# REV1.net
KiCad netlist of a schematic drawn in EAGLE
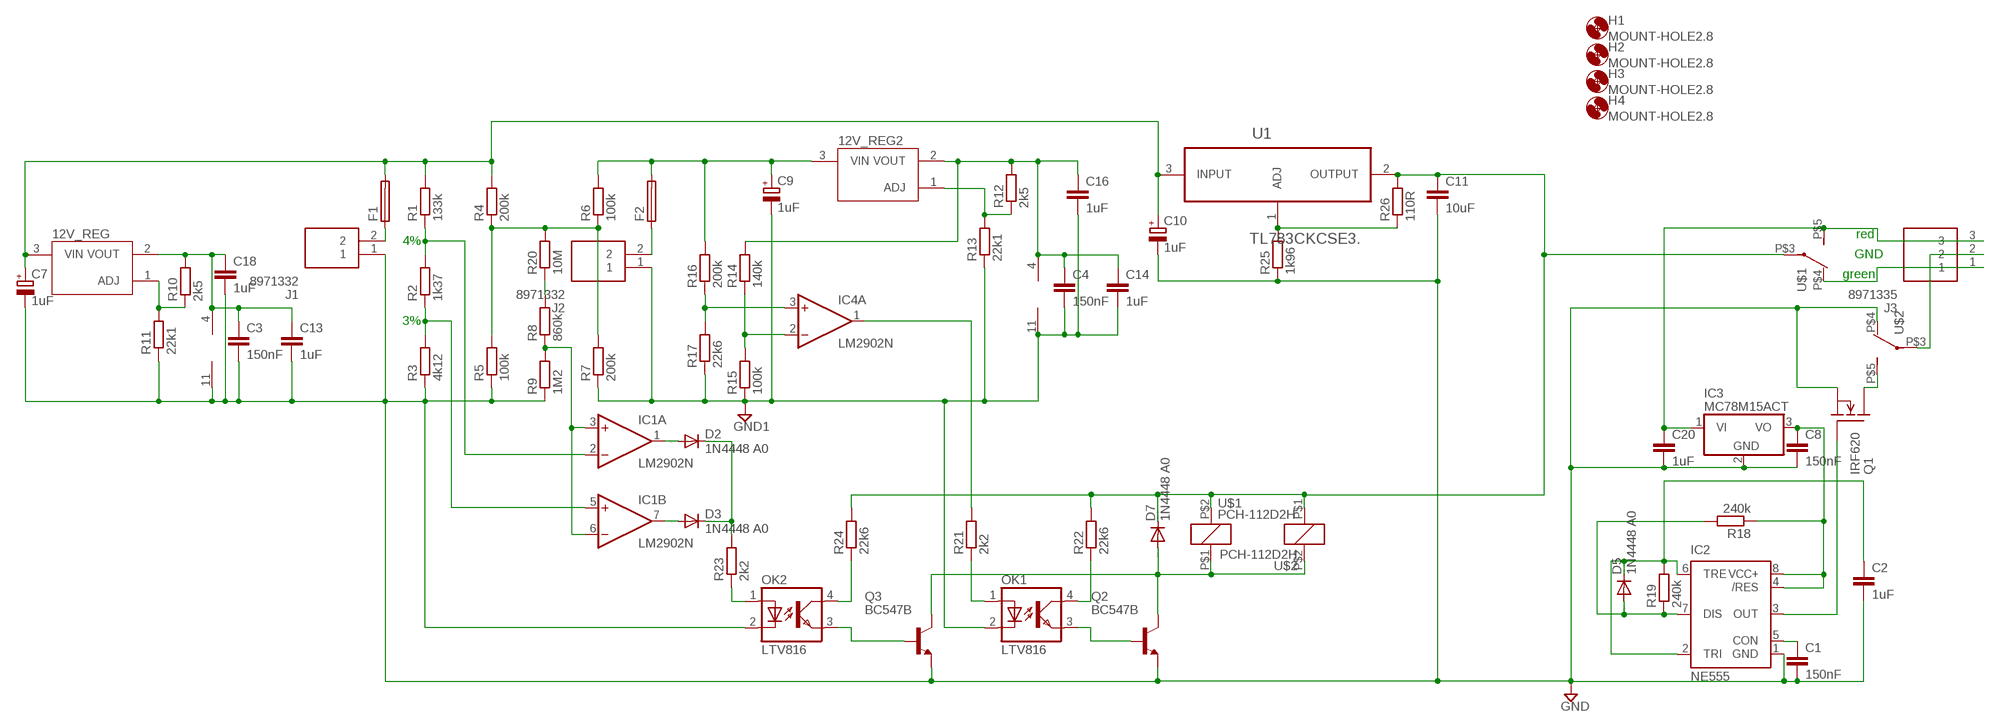
[diagram p0: schematic, sheet 1]

(export (version "E")
  (design (tool "Eeschema 10.0.6"))
  (components
    (comp (ref "12V_REG")
      (value "LR8LR8")
      (footprint "eagle-import:TO92-LINE")
      (libsource (lib "eagle-import") (part "LR8LR8"))
    )
    (comp (ref "12V_REG2")
      (value "LR8LR8")
      (footprint "eagle-import:TO92-LINE")
      (libsource (lib "eagle-import") (part "LR8LR8"))
    )
    (comp (ref "C1")
      (value "150nF")
      (footprint "eagle-import:C050-024X044")
      (libsource (lib "eagle-import") (part "C-EU050-024X044"))
    )
    (comp (ref "C2")
      (value "1uF")
      (footprint "eagle-import:C025-030X050")
      (libsource (lib "eagle-import") (part "C-EU025-030X050"))
    )
    (comp (ref "C3")
      (value "150nF")
      (footprint "eagle-import:C050-024X044")
      (libsource (lib "eagle-import") (part "C-EU050-024X044"))
    )
    (comp (ref "C4")
      (value "150nF")
      (footprint "eagle-import:C050-024X044")
      (libsource (lib "eagle-import") (part "C-EU050-024X044"))
    )
    (comp (ref "C7")
      (value "1uF")
      (footprint "eagle-import:E3,5-8")
      (libsource (lib "eagle-import") (part "CPOL-EUE3.5-8"))
    )
    (comp (ref "C8")
      (value "150nF")
      (footprint "eagle-import:C050-024X044")
      (libsource (lib "eagle-import") (part "C-EU050-024X044"))
    )
    (comp (ref "C9")
      (value "1uF")
      (footprint "eagle-import:E3,5-8")
      (libsource (lib "eagle-import") (part "CPOL-EUE3.5-8"))
    )
    (comp (ref "C10")
      (value "1uF")
      (footprint "eagle-import:E3,5-8")
      (libsource (lib "eagle-import") (part "CPOL-EUE3.5-8"))
    )
    (comp (ref "C11")
      (value "10uF")
      (footprint "eagle-import:C050-075X075")
      (libsource (lib "eagle-import") (part "C-EU050-075X075"))
    )
    (comp (ref "C13")
      (value "1uF")
      (footprint "eagle-import:C025-030X050")
      (libsource (lib "eagle-import") (part "C-EU025-030X050"))
    )
    (comp (ref "C14")
      (value "1uF")
      (footprint "eagle-import:C025-030X050")
      (libsource (lib "eagle-import") (part "C-EU025-030X050"))
    )
    (comp (ref "C16")
      (value "1uF")
      (footprint "eagle-import:C025-030X050")
      (libsource (lib "eagle-import") (part "C-EU025-030X050"))
    )
    (comp (ref "C18")
      (value "1uF")
      (footprint "eagle-import:C025-030X050")
      (libsource (lib "eagle-import") (part "C-EU025-030X050"))
    )
    (comp (ref "C20")
      (value "1uF")
      (footprint "eagle-import:C025-030X050")
      (libsource (lib "eagle-import") (part "C-EU025-030X050"))
    )
    (comp (ref "D2")
      (value "1N4448 A0")
      (footprint "eagle-import:DO35-10")
      (libsource (lib "eagle-import") (part "1N4446"))
    )
    (comp (ref "D3")
      (value "1N4448 A0")
      (footprint "eagle-import:DO35-10")
      (libsource (lib "eagle-import") (part "1N4446"))
    )
    (comp (ref "D5")
      (value "1N4448 A0")
      (footprint "eagle-import:DO35-10")
      (libsource (lib "eagle-import") (part "1N4446"))
    )
    (comp (ref "D7")
      (value "1N4448 A0")
      (footprint "eagle-import:DO35-10")
      (libsource (lib "eagle-import") (part "1N4446"))
    )
    (comp (ref "F1")
      (value "GSH15")
      (footprint "eagle-import:GSH15")
      (fields (field (name "MPN") "64900001039"))
      (libsource (lib "eagle-import") (part "GSH15"))
    )
    (comp (ref "F2")
      (value "GSH15")
      (footprint "eagle-import:GSH15")
      (fields (field (name "MPN") "64900001039"))
      (libsource (lib "eagle-import") (part "GSH15"))
    )
    (comp (ref "H1")
      (value "MOUNT-HOLE2.8")
      (footprint "eagle-import:2,8")
      (libsource (lib "eagle-import") (part "MOUNT-HOLE2.8"))
    )
    (comp (ref "H2")
      (value "MOUNT-HOLE2.8")
      (footprint "eagle-import:2,8")
      (libsource (lib "eagle-import") (part "MOUNT-HOLE2.8"))
    )
    (comp (ref "H3")
      (value "MOUNT-HOLE2.8")
      (footprint "eagle-import:2,8")
      (libsource (lib "eagle-import") (part "MOUNT-HOLE2.8"))
    )
    (comp (ref "H4")
      (value "MOUNT-HOLE2.8")
      (footprint "eagle-import:2,8")
      (libsource (lib "eagle-import") (part "MOUNT-HOLE2.8"))
    )
    (comp (ref "IC1")
      (value "LM2902N")
      (footprint "eagle-import:DIL14")
      (libsource (lib "eagle-import") (part "LM2902N"))
    )
    (comp (ref "IC2")
      (value "NE555")
      (footprint "eagle-import:DIL-08")
      (fields (field (name "MF") "Arrow Electronics") (field (name "MPN") "NE555N"))
      (libsource (lib "eagle-import") (part "NE555"))
    )
    (comp (ref "IC3")
      (value "MC78M15ACT")
      (footprint "eagle-import:TO220V")
      (libsource (lib "eagle-import") (part "MC78MT15AC"))
    )
    (comp (ref "IC4")
      (value "LM2902N")
      (footprint "eagle-import:DIL14")
      (libsource (lib "eagle-import") (part "LM2902N"))
    )
    (comp (ref "J1")
      (value "8971332")
      (footprint "eagle-import:SHDR2W90P0X350_1X2_700X700X850")
      (libsource (lib "eagle-import") (part "8971332"))
    )
    (comp (ref "J2")
      (value "8971332")
      (footprint "eagle-import:SHDR2W90P0X350_1X2_700X700X850")
      (libsource (lib "eagle-import") (part "8971332"))
    )
    (comp (ref "J3")
      (value "8971335")
      (footprint "eagle-import:SHDR3W90P0X350_1X3_1050X700X85")
      (libsource (lib "eagle-import") (part "8971335"))
    )
    (comp (ref "OK1")
      (value "LTV816")
      (footprint "eagle-import:DIL04")
      (libsource (lib "eagle-import") (part "LTV816"))
    )
    (comp (ref "OK2")
      (value "LTV816")
      (footprint "eagle-import:DIL04")
      (libsource (lib "eagle-import") (part "LTV816"))
    )
    (comp (ref "Q1")
      (value "IRF620")
      (footprint "eagle-import:TO220")
      (libsource (lib "eagle-import") (part "IRF620"))
    )
    (comp (ref "Q2")
      (value "BC547B")
      (footprint "eagle-import:TO92")
      (libsource (lib "eagle-import") (part "BC547B"))
    )
    (comp (ref "Q3")
      (value "BC547B")
      (footprint "eagle-import:TO92")
      (libsource (lib "eagle-import") (part "BC547B"))
    )
    (comp (ref "R1")
      (value "133k")
      (footprint "eagle-import:0207_10")
      (libsource (lib "eagle-import") (part "R-EU_0207/10"))
    )
    (comp (ref "R2")
      (value "1k37")
      (footprint "eagle-import:0207_10")
      (libsource (lib "eagle-import") (part "R-EU_0207/10"))
    )
    (comp (ref "R3")
      (value "4k12")
      (footprint "eagle-import:0207_10")
      (libsource (lib "eagle-import") (part "R-EU_0207/10"))
    )
    (comp (ref "R4")
      (value "200k")
      (footprint "eagle-import:0207_10")
      (libsource (lib "eagle-import") (part "R-EU_0207/10"))
    )
    (comp (ref "R5")
      (value "100k")
      (footprint "eagle-import:0207_10")
      (libsource (lib "eagle-import") (part "R-EU_0207/10"))
    )
    (comp (ref "R6")
      (value "100k")
      (footprint "eagle-import:0207_10")
      (libsource (lib "eagle-import") (part "R-EU_0207/10"))
    )
    (comp (ref "R7")
      (value "200k")
      (footprint "eagle-import:0207_10")
      (libsource (lib "eagle-import") (part "R-EU_0207/10"))
    )
    (comp (ref "R8")
      (value "860k")
      (footprint "eagle-import:0207_10")
      (libsource (lib "eagle-import") (part "R-EU_0207/10"))
    )
    (comp (ref "R9")
      (value "1M2")
      (footprint "eagle-import:0207_10")
      (libsource (lib "eagle-import") (part "R-EU_0207/10"))
    )
    (comp (ref "R10")
      (value "2k5")
      (footprint "eagle-import:0207_10")
      (libsource (lib "eagle-import") (part "R-EU_0207/10"))
    )
    (comp (ref "R11")
      (value "22k1")
      (footprint "eagle-import:0207_10")
      (libsource (lib "eagle-import") (part "R-EU_0207/10"))
    )
    (comp (ref "R12")
      (value "2k5")
      (footprint "eagle-import:0207_10")
      (libsource (lib "eagle-import") (part "R-EU_0207/10"))
    )
    (comp (ref "R13")
      (value "22k1")
      (footprint "eagle-import:0207_10")
      (libsource (lib "eagle-import") (part "R-EU_0207/10"))
    )
    (comp (ref "R14")
      (value "140k")
      (footprint "eagle-import:0207_10")
      (libsource (lib "eagle-import") (part "R-EU_0207/10"))
    )
    (comp (ref "R15")
      (value "100k")
      (footprint "eagle-import:0207_10")
      (libsource (lib "eagle-import") (part "R-EU_0207/10"))
    )
    (comp (ref "R16")
      (value "200k")
      (footprint "eagle-import:0207_10")
      (libsource (lib "eagle-import") (part "R-EU_0207/10"))
    )
    (comp (ref "R17")
      (value "22k6")
      (footprint "eagle-import:0207_10")
      (libsource (lib "eagle-import") (part "R-EU_0207/10"))
    )
    (comp (ref "R18")
      (value "240k")
      (footprint "eagle-import:0207_10")
      (libsource (lib "eagle-import") (part "R-EU_0207/10"))
    )
    (comp (ref "R19")
      (value "240k")
      (footprint "eagle-import:0207_10")
      (libsource (lib "eagle-import") (part "R-EU_0207/10"))
    )
    (comp (ref "R20")
      (value "10M")
      (footprint "eagle-import:0207_10")
      (libsource (lib "eagle-import") (part "R-EU_0207/10"))
    )
    (comp (ref "R21")
      (value "2k2")
      (footprint "eagle-import:0207_10")
      (libsource (lib "eagle-import") (part "R-EU_0207/10"))
    )
    (comp (ref "R22")
      (value "22k6")
      (footprint "eagle-import:0207_10")
      (libsource (lib "eagle-import") (part "R-EU_0207/10"))
    )
    (comp (ref "R23")
      (value "2k2")
      (footprint "eagle-import:0207_10")
      (libsource (lib "eagle-import") (part "R-EU_0207/10"))
    )
    (comp (ref "R24")
      (value "22k6")
      (footprint "eagle-import:0207_10")
      (libsource (lib "eagle-import") (part "R-EU_0207/10"))
    )
    (comp (ref "R25")
      (value "1k96")
      (footprint "eagle-import:0309_10")
      (libsource (lib "eagle-import") (part "R-EU_0309/10"))
    )
    (comp (ref "R26")
      (value "110R")
      (footprint "eagle-import:0309_10")
      (libsource (lib "eagle-import") (part "R-EU_0309/10"))
    )
    (comp (ref "U$1")
      (value "PCH-112D2H")
      (footprint "eagle-import:PCH-112D2H")
      (libsource (lib "eagle-import") (part "PCH-112D2H"))
    )
    (comp (ref "U$2")
      (value "PCH-112D2H")
      (footprint "eagle-import:PCH-112D2H")
      (libsource (lib "eagle-import") (part "PCH-112D2H"))
    )
    (comp (ref "U1")
      (value "TL783CKCSE3.")
      (footprint "eagle-import:TO254P457X1016X2222-3P")
      (libsource (lib "eagle-import") (part "TL783CKCSE3."))
    )
  )
  (nets
    (net (code "1") (name "GND") (class "Default")
      (node (ref "C1") (pin "2") (pinfunction "2_2") (pintype "passive"))
      (node (ref "C10") (pin "-") (pinfunction "-_-") (pintype "passive"))
      (node (ref "C11") (pin "2") (pinfunction "2_2") (pintype "passive"))
      (node (ref "C13") (pin "2") (pinfunction "2_2") (pintype "passive"))
      (node (ref "C18") (pin "2") (pinfunction "2_2") (pintype "passive"))
      (node (ref "C2") (pin "2") (pinfunction "2_2") (pintype "passive"))
      (node (ref "C20") (pin "2") (pinfunction "2_2") (pintype "passive"))
      (node (ref "C3") (pin "2") (pinfunction "2_2") (pintype "passive"))
      (node (ref "C7") (pin "-") (pinfunction "-_-") (pintype "passive"))
      (node (ref "C8") (pin "2") (pinfunction "2_2") (pintype "passive"))
      (node (ref "IC1") (pin "11") (pinfunction "V-_11") (pintype "power_in"))
      (node (ref "IC2") (pin "1") (pinfunction "GND_1") (pintype "power_in"))
      (node (ref "IC3") (pin "2") (pinfunction "GND_2") (pintype "passive"))
      (node (ref "J1") (pin "1") (pinfunction "1_1") (pintype "bidirectional"))
      (node (ref "OK2") (pin "2") (pinfunction "C_2") (pintype "passive"))
      (node (ref "Q1") (pin "3") (pinfunction "S_3") (pintype "passive"))
      (node (ref "Q2") (pin "1") (pinfunction "E_1") (pintype "passive"))
      (node (ref "Q3") (pin "1") (pinfunction "E_1") (pintype "passive"))
      (node (ref "R11") (pin "1") (pinfunction "1_1") (pintype "passive"))
      (node (ref "R25") (pin "1") (pinfunction "1_1") (pintype "passive"))
      (node (ref "R3") (pin "1") (pinfunction "1_1") (pintype "passive"))
      (node (ref "R5") (pin "1") (pinfunction "1_1") (pintype "passive"))
      (node (ref "R9") (pin "1") (pinfunction "1_1") (pintype "passive"))
      (node (ref "U$2") (pin "P$4") (pinfunction "O_P$4") (pintype "passive"))
    )
    (net (code "2") (name "GND1") (class "Default")
      (node (ref "C14") (pin "2") (pinfunction "2_2") (pintype "passive"))
      (node (ref "C16") (pin "2") (pinfunction "2_2") (pintype "passive"))
      (node (ref "C4") (pin "2") (pinfunction "2_2") (pintype "passive"))
      (node (ref "C9") (pin "-") (pinfunction "-_-") (pintype "passive"))
      (node (ref "IC4") (pin "11") (pinfunction "V-_11") (pintype "power_in"))
      (node (ref "J2") (pin "1") (pinfunction "1_1") (pintype "bidirectional"))
      (node (ref "OK1") (pin "2") (pinfunction "C_2") (pintype "passive"))
      (node (ref "R13") (pin "1") (pinfunction "1_1") (pintype "passive"))
      (node (ref "R15") (pin "1") (pinfunction "1_1") (pintype "passive"))
      (node (ref "R17") (pin "1") (pinfunction "1_1") (pintype "passive"))
      (node (ref "R7") (pin "1") (pinfunction "1_1") (pintype "passive"))
    )
    (net (code "3") (name "Net-(12V_REG-ADJ)") (class "Default")
      (node (ref "12V_REG") (pin "1") (pinfunction "ADJ_1") (pintype "bidirectional"))
      (node (ref "R10") (pin "1") (pinfunction "1_1") (pintype "passive"))
      (node (ref "R11") (pin "2") (pinfunction "2_2") (pintype "passive"))
    )
    (net (code "4") (name "Net-(12V_REG-VIN)") (class "Default")
      (node (ref "12V_REG") (pin "3") (pinfunction "VIN_3") (pintype "bidirectional"))
      (node (ref "C10") (pin "+") (pinfunction "+_+") (pintype "passive"))
      (node (ref "C7") (pin "+") (pinfunction "+_+") (pintype "passive"))
      (node (ref "F1") (pin "2") (pinfunction "2_2") (pintype "passive"))
      (node (ref "R1") (pin "2") (pinfunction "2_2") (pintype "passive"))
      (node (ref "R4") (pin "2") (pinfunction "2_2") (pintype "passive"))
      (node (ref "U1") (pin "3") (pinfunction "INPUT_3") (pintype "input"))
    )
    (net (code "5") (name "Net-(12V_REG-VOUT)") (class "Default")
      (node (ref "12V_REG") (pin "2") (pinfunction "VOUT_2") (pintype "bidirectional"))
      (node (ref "C13") (pin "1") (pinfunction "1_1") (pintype "passive"))
      (node (ref "C18") (pin "1") (pinfunction "1_1") (pintype "passive"))
      (node (ref "C3") (pin "1") (pinfunction "1_1") (pintype "passive"))
      (node (ref "IC1") (pin "4") (pinfunction "V+_4") (pintype "power_in"))
      (node (ref "R10") (pin "2") (pinfunction "2_2") (pintype "passive"))
    )
    (net (code "6") (name "Net-(12V_REG2-ADJ)") (class "Default")
      (node (ref "12V_REG2") (pin "1") (pinfunction "ADJ_1") (pintype "bidirectional"))
      (node (ref "R12") (pin "1") (pinfunction "1_1") (pintype "passive"))
      (node (ref "R13") (pin "2") (pinfunction "2_2") (pintype "passive"))
    )
    (net (code "7") (name "Net-(12V_REG2-VIN)") (class "Default")
      (node (ref "12V_REG2") (pin "3") (pinfunction "VIN_3") (pintype "bidirectional"))
      (node (ref "C9") (pin "+") (pinfunction "+_+") (pintype "passive"))
      (node (ref "F2") (pin "2") (pinfunction "2_2") (pintype "passive"))
      (node (ref "R16") (pin "2") (pinfunction "2_2") (pintype "passive"))
      (node (ref "R6") (pin "2") (pinfunction "2_2") (pintype "passive"))
    )
    (net (code "8") (name "Net-(12V_REG2-VOUT)") (class "Default")
      (node (ref "12V_REG2") (pin "2") (pinfunction "VOUT_2") (pintype "bidirectional"))
      (node (ref "C14") (pin "1") (pinfunction "1_1") (pintype "passive"))
      (node (ref "C16") (pin "1") (pinfunction "1_1") (pintype "passive"))
      (node (ref "C4") (pin "1") (pinfunction "1_1") (pintype "passive"))
      (node (ref "IC4") (pin "4") (pinfunction "V+_4") (pintype "power_in"))
      (node (ref "R12") (pin "2") (pinfunction "2_2") (pintype "passive"))
      (node (ref "R14") (pin "2") (pinfunction "2_2") (pintype "passive"))
    )
    (net (code "9") (name "Net-(D2-PadC)") (class "Default")
      (node (ref "D2") (pin "C") (pinfunction "C_C") (pintype "passive"))
      (node (ref "D3") (pin "C") (pinfunction "C_C") (pintype "passive"))
      (node (ref "R23") (pin "2") (pinfunction "2_2") (pintype "passive"))
    )
    (net (code "10") (name "Net-(F1-Pad1)") (class "Default")
      (node (ref "F1") (pin "1") (pinfunction "1_1") (pintype "passive"))
      (node (ref "J1") (pin "2") (pinfunction "2_2") (pintype "bidirectional"))
    )
    (net (code "11") (name "Net-(F2-Pad1)") (class "Default")
      (node (ref "F2") (pin "1") (pinfunction "1_1") (pintype "passive"))
      (node (ref "J2") (pin "2") (pinfunction "2_2") (pintype "bidirectional"))
    )
    (net (code "12") (name "Net-(IC1A-+IN)") (class "Default")
      (node (ref "IC1") (pin "3") (pinfunction "+IN_3") (pintype "input"))
      (node (ref "IC1") (pin "6") (pinfunction "-IN_6") (pintype "input"))
      (node (ref "R8") (pin "1") (pinfunction "1_1") (pintype "passive"))
      (node (ref "R9") (pin "2") (pinfunction "2_2") (pintype "passive"))
    )
    (net (code "13") (name "Net-(IC1A--IN)") (class "Default")
      (node (ref "IC1") (pin "2") (pinfunction "-IN_2") (pintype "input"))
      (node (ref "R1") (pin "1") (pinfunction "1_1") (pintype "passive"))
      (node (ref "R2") (pin "2") (pinfunction "2_2") (pintype "passive"))
    )
    (net (code "14") (name "Net-(IC1A-OUT)") (class "Default")
      (node (ref "D2") (pin "A") (pinfunction "A_A") (pintype "passive"))
      (node (ref "IC1") (pin "1") (pinfunction "OUT_1") (pintype "output"))
    )
    (net (code "15") (name "Net-(IC1B-+IN)") (class "Default")
      (node (ref "IC1") (pin "5") (pinfunction "+IN_5") (pintype "input"))
      (node (ref "R2") (pin "1") (pinfunction "1_1") (pintype "passive"))
      (node (ref "R3") (pin "2") (pinfunction "2_2") (pintype "passive"))
    )
    (net (code "16") (name "Net-(IC1B-OUT)") (class "Default")
      (node (ref "D3") (pin "A") (pinfunction "A_A") (pintype "passive"))
      (node (ref "IC1") (pin "7") (pinfunction "OUT_7") (pintype "output"))
    )
    (net (code "17") (name "Net-(IC2-CON)") (class "Default")
      (node (ref "C1") (pin "1") (pinfunction "1_1") (pintype "passive"))
      (node (ref "IC2") (pin "5") (pinfunction "CON_5") (pintype "input"))
    )
    (net (code "18") (name "Net-(IC2-DIS)") (class "Default")
      (node (ref "D5") (pin "A") (pinfunction "A_A") (pintype "passive"))
      (node (ref "IC2") (pin "7") (pinfunction "DIS_7") (pintype "input"))
      (node (ref "R18") (pin "2") (pinfunction "2_2") (pintype "passive"))
      (node (ref "R19") (pin "1") (pinfunction "1_1") (pintype "passive"))
    )
    (net (code "19") (name "Net-(IC2-OUT)") (class "Default")
      (node (ref "IC2") (pin "3") (pinfunction "OUT_3") (pintype "output"))
      (node (ref "Q1") (pin "1") (pinfunction "G_1") (pintype "passive"))
    )
    (net (code "20") (name "Net-(IC2-TRE)") (class "Default")
      (node (ref "C2") (pin "1") (pinfunction "1_1") (pintype "passive"))
      (node (ref "D5") (pin "C") (pinfunction "C_C") (pintype "passive"))
      (node (ref "IC2") (pin "2") (pinfunction "TRI_2") (pintype "input"))
      (node (ref "IC2") (pin "6") (pinfunction "TRE_6") (pintype "input"))
      (node (ref "R19") (pin "2") (pinfunction "2_2") (pintype "passive"))
    )
    (net (code "21") (name "Net-(IC2-VCC+)") (class "Default")
      (node (ref "C8") (pin "1") (pinfunction "1_1") (pintype "passive"))
      (node (ref "IC2") (pin "4") (pinfunction "/RES_4") (pintype "input"))
      (node (ref "IC2") (pin "8") (pinfunction "VCC+_8") (pintype "power_in"))
      (node (ref "IC3") (pin "3") (pinfunction "VO_3") (pintype "passive"))
      (node (ref "R18") (pin "1") (pinfunction "1_1") (pintype "passive"))
    )
    (net (code "22") (name "Net-(IC3-VI)") (class "Default")
      (node (ref "C20") (pin "1") (pinfunction "1_1") (pintype "passive"))
      (node (ref "IC3") (pin "1") (pinfunction "VI_1") (pintype "input"))
      (node (ref "J3") (pin "3") (pinfunction "3_3") (pintype "bidirectional"))
      (node (ref "U$1") (pin "P$5") (pinfunction "S_P$5") (pintype "passive"))
    )
    (net (code "23") (name "Net-(IC4A-+IN)") (class "Default")
      (node (ref "IC4") (pin "3") (pinfunction "+IN_3") (pintype "input"))
      (node (ref "R16") (pin "1") (pinfunction "1_1") (pintype "passive"))
      (node (ref "R17") (pin "2") (pinfunction "2_2") (pintype "passive"))
    )
    (net (code "24") (name "Net-(IC4A--IN)") (class "Default")
      (node (ref "IC4") (pin "2") (pinfunction "-IN_2") (pintype "input"))
      (node (ref "R14") (pin "1") (pinfunction "1_1") (pintype "passive"))
      (node (ref "R15") (pin "2") (pinfunction "2_2") (pintype "passive"))
    )
    (net (code "25") (name "Net-(IC4A-OUT)") (class "Default")
      (node (ref "IC4") (pin "1") (pinfunction "OUT_1") (pintype "output"))
      (node (ref "R21") (pin "2") (pinfunction "2_2") (pintype "passive"))
    )
    (net (code "26") (name "Net-(OK1-A)") (class "Default")
      (node (ref "OK1") (pin "1") (pinfunction "A_1") (pintype "passive"))
      (node (ref "R21") (pin "1") (pinfunction "1_1") (pintype "passive"))
    )
    (net (code "27") (name "Net-(OK1-COL)") (class "Default")
      (node (ref "OK1") (pin "4") (pinfunction "COL_4") (pintype "passive"))
      (node (ref "R22") (pin "1") (pinfunction "1_1") (pintype "passive"))
    )
    (net (code "28") (name "Net-(OK1-EMIT)") (class "Default")
      (node (ref "OK1") (pin "3") (pinfunction "EMIT_3") (pintype "passive"))
      (node (ref "Q2") (pin "2") (pinfunction "B_2") (pintype "passive"))
    )
    (net (code "29") (name "Net-(OK2-A)") (class "Default")
      (node (ref "OK2") (pin "1") (pinfunction "A_1") (pintype "passive"))
      (node (ref "R23") (pin "1") (pinfunction "1_1") (pintype "passive"))
    )
    (net (code "30") (name "Net-(OK2-COL)") (class "Default")
      (node (ref "OK2") (pin "4") (pinfunction "COL_4") (pintype "passive"))
      (node (ref "R24") (pin "1") (pinfunction "1_1") (pintype "passive"))
    )
    (net (code "31") (name "Net-(OK2-EMIT)") (class "Default")
      (node (ref "OK2") (pin "3") (pinfunction "EMIT_3") (pintype "passive"))
      (node (ref "Q3") (pin "2") (pinfunction "B_2") (pintype "passive"))
    )
    (net (code "32") (name "Net-(Q1-D)") (class "Default")
      (node (ref "Q1") (pin "2") (pinfunction "D_2") (pintype "passive"))
      (node (ref "U$2") (pin "P$5") (pinfunction "S_P$5") (pintype "passive"))
    )
    (net (code "33") (name "Net-(Q2-C)") (class "Default")
      (node (ref "D7") (pin "A") (pinfunction "A_A") (pintype "passive"))
      (node (ref "Q2") (pin "3") (pinfunction "C_3") (pintype "passive"))
      (node (ref "Q3") (pin "3") (pinfunction "C_3") (pintype "passive"))
      (node (ref "U$1") (pin "P$1") (pinfunction "2_P$1") (pintype "passive"))
      (node (ref "U$2") (pin "P$2") (pinfunction "1_P$2") (pintype "passive"))
    )
    (net (code "34") (name "Net-(R20-Pad1)") (class "Default")
      (node (ref "R20") (pin "1") (pinfunction "1_1") (pintype "passive"))
      (node (ref "R8") (pin "2") (pinfunction "2_2") (pintype "passive"))
    )
    (net (code "35") (name "Net-(R20-Pad2)") (class "Default")
      (node (ref "R20") (pin "2") (pinfunction "2_2") (pintype "passive"))
      (node (ref "R4") (pin "1") (pinfunction "1_1") (pintype "passive"))
      (node (ref "R5") (pin "2") (pinfunction "2_2") (pintype "passive"))
      (node (ref "R6") (pin "1") (pinfunction "1_1") (pintype "passive"))
      (node (ref "R7") (pin "2") (pinfunction "2_2") (pintype "passive"))
    )
    (net (code "36") (name "Net-(U$1A-1)") (class "Default")
      (node (ref "C11") (pin "1") (pinfunction "1_1") (pintype "passive"))
      (node (ref "D7") (pin "C") (pinfunction "C_C") (pintype "passive"))
      (node (ref "R22") (pin "2") (pinfunction "2_2") (pintype "passive"))
      (node (ref "R24") (pin "2") (pinfunction "2_2") (pintype "passive"))
      (node (ref "R26") (pin "2") (pinfunction "2_2") (pintype "passive"))
      (node (ref "U$1") (pin "P$2") (pinfunction "1_P$2") (pintype "passive"))
      (node (ref "U$1") (pin "P$3") (pinfunction "P_P$3") (pintype "passive"))
      (node (ref "U$2") (pin "P$1") (pinfunction "2_P$1") (pintype "passive"))
      (node (ref "U1") (pin "2") (pinfunction "OUTPUT_2") (pintype "output"))
    )
    (net (code "37") (name "Net-(U$1B-O)") (class "Default")
      (node (ref "J3") (pin "1") (pinfunction "1_1") (pintype "bidirectional"))
      (node (ref "U$1") (pin "P$4") (pinfunction "O_P$4") (pintype "passive"))
    )
    (net (code "38") (name "Net-(U$2B-P)") (class "Default")
      (node (ref "J3") (pin "2") (pinfunction "2_2") (pintype "bidirectional"))
      (node (ref "U$2") (pin "P$3") (pinfunction "P_P$3") (pintype "passive"))
    )
    (net (code "39") (name "Net-(U1-ADJ)") (class "Default")
      (node (ref "R25") (pin "2") (pinfunction "2_2") (pintype "passive"))
      (node (ref "R26") (pin "1") (pinfunction "1_1") (pintype "passive"))
      (node (ref "U1") (pin "1") (pinfunction "ADJ_1") (pintype "passive"))
    )
  )
)
